# attiny_x4_blink.net
KiCad netlist of a schematic drawn in EAGLE
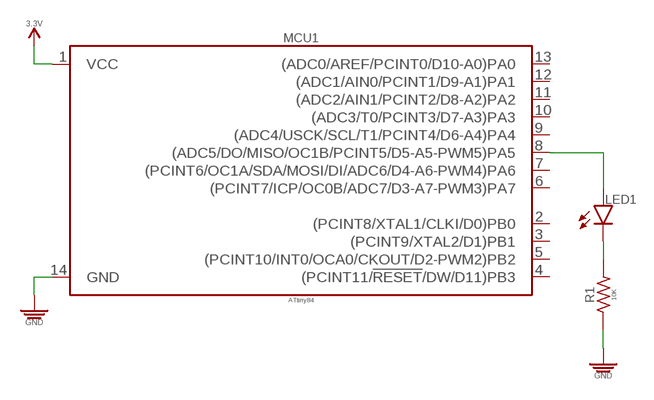
[diagram p0: schematic, sheet 1]

(export (version "E")
  (design (tool "Eeschema 10.0.6"))
  (components
    (comp (ref "LED1")
      (value "LED_PTH_T-1_3/4_5MM_NO-COLOR")
      (footprint "eagle-import:LED_PTH_T-1_3_4_5MM")
      (libsource (lib "eagle-import") (part "LED_PTH_T-1_3/4_5MM_NO-COLOR"))
    )
    (comp (ref "MCU1")
      (value "ATtiny84")
      (footprint "eagle-import:DIP794W46P254L1919H533Q14B_DIP-14_CONNECTOR")
      (fields (field (name "MFR") "Microchip Technology") (field (name "MPN") "ATTINY84A-PU"))
      (libsource (lib "eagle-import") (part "ATTINY-X4_DIP-14_ATTINY-84_CONNECTOR"))
    )
    (comp (ref "R1")
      (value "10K")
      (footprint "eagle-import:RESAD660W45L340D190B")
      (fields (field (name "MFR") "Yageo") (field (name "MPN") "CFR-12JB-52-10K"))
      (libsource (lib "eagle-import") (part "10KΩ_PTH-204/7_1/6W-5%"))
    )
  )
  (nets
    (net (code "1") (name "3.3V") (class "Default")
      (node (ref "MCU1") (pin "1") (pinfunction "VCC_1") (pintype "passive"))
    )
    (net (code "2") (name "GND") (class "Default")
      (node (ref "MCU1") (pin "14") (pinfunction "GND_14") (pintype "passive"))
      (node (ref "R1") (pin "1") (pinfunction "1_1") (pintype "passive"))
    )
    (net (code "3") (name "Net-(LED1-PadK)") (class "Default")
      (node (ref "LED1") (pin "K") (pinfunction "K_K") (pintype "passive"))
      (node (ref "R1") (pin "2") (pinfunction "2_2") (pintype "passive"))
    )
    (net (code "4") (name "Net-(MCU1-(ADC5{slash}DO{slash}MISO{slash}OC1B{slash}PCINT5{slash}D5-A5-PWM5)PA5)") (class "Default")
      (node (ref "LED1") (pin "A") (pinfunction "A_A") (pintype "passive"))
      (node (ref "MCU1") (pin "8") (pinfunction "(ADC5/DO/MISO/OC1B/PCINT5/D5-A5-PWM5)PA5_8") (pintype "bidirectional"))
    )
    (net (code "5") (name "unconnected-(MCU1-(ADC0{slash}AREF{slash}PCINT0{slash}D10-A0)PA0-Pad13)") (class "Default")
      (node (ref "MCU1") (pin "13") (pinfunction "(ADC0/AREF/PCINT0/D10-A0)PA0_13") (pintype "bidirectional"))
    )
    (net (code "6") (name "unconnected-(MCU1-(ADC1{slash}AIN0{slash}PCINT1{slash}D9-A1)PA1-Pad12)") (class "Default")
      (node (ref "MCU1") (pin "12") (pinfunction "(ADC1/AIN0/PCINT1/D9-A1)PA1_12") (pintype "bidirectional"))
    )
    (net (code "7") (name "unconnected-(MCU1-(ADC2{slash}AIN1{slash}PCINT2{slash}D8-A2)PA2-Pad11)") (class "Default")
      (node (ref "MCU1") (pin "11") (pinfunction "(ADC2/AIN1/PCINT2/D8-A2)PA2_11") (pintype "bidirectional"))
    )
    (net (code "8") (name "unconnected-(MCU1-(ADC3{slash}T0{slash}PCINT3{slash}D7-A3)PA3-Pad10)") (class "Default")
      (node (ref "MCU1") (pin "10") (pinfunction "(ADC3/T0/PCINT3/D7-A3)PA3_10") (pintype "bidirectional"))
    )
    (net (code "9") (name "unconnected-(MCU1-(ADC4{slash}USCK{slash}SCL{slash}T1{slash}PCINT4{slash}D6-A4)PA4-Pad9)") (class "Default")
      (node (ref "MCU1") (pin "9") (pinfunction "(ADC4/USCK/SCL/T1/PCINT4/D6-A4)PA4_9") (pintype "bidirectional"))
    )
    (net (code "10") (name "unconnected-(MCU1-(PCINT6{slash}OC1A{slash}SDA{slash}MOSI{slash}DI{slash}ADC6{slash}D4-A6-PWM4)PA6-Pad7)") (class "Default")
      (node (ref "MCU1") (pin "7") (pinfunction "(PCINT6/OC1A/SDA/MOSI/DI/ADC6/D4-A6-PWM4)PA6_7") (pintype "bidirectional"))
    )
    (net (code "11") (name "unconnected-(MCU1-(PCINT7{slash}ICP{slash}OC0B{slash}ADC7{slash}D3-A7-PWM3)PA7-Pad6)") (class "Default")
      (node (ref "MCU1") (pin "6") (pinfunction "(PCINT7/ICP/OC0B/ADC7/D3-A7-PWM3)PA7_6") (pintype "bidirectional"))
    )
    (net (code "12") (name "unconnected-(MCU1-(PCINT8{slash}XTAL1{slash}CLKI{slash}D0)PB0-Pad2)") (class "Default")
      (node (ref "MCU1") (pin "2") (pinfunction "(PCINT8/XTAL1/CLKI/D0)PB0_2") (pintype "bidirectional"))
    )
    (net (code "13") (name "unconnected-(MCU1-(PCINT9{slash}XTAL2{slash}D1)PB1-Pad3)") (class "Default")
      (node (ref "MCU1") (pin "3") (pinfunction "(PCINT9/XTAL2/D1)PB1_3") (pintype "bidirectional"))
    )
    (net (code "14") (name "unconnected-(MCU1-(PCINT10{slash}INT0{slash}OCA0{slash}CKOUT{slash}D2-PWM2)PB2-Pad5)") (class "Default")
      (node (ref "MCU1") (pin "5") (pinfunction "(PCINT10/INT0/OCA0/CKOUT/D2-PWM2)PB2_5") (pintype "bidirectional"))
    )
    (net (code "15") (name "unconnected-(MCU1-(PCINT11{slash}~{RESET}{slash}DW{slash}D11)PB3-Pad4)") (class "Default")
      (node (ref "MCU1") (pin "4") (pinfunction "(PCINT11/~{RESET}/DW/D11)PB3_4") (pintype "bidirectional"))
    )
  )
)
